# airball_sensor_board_v4.net
KiCad netlist of a schematic drawn in EAGLE
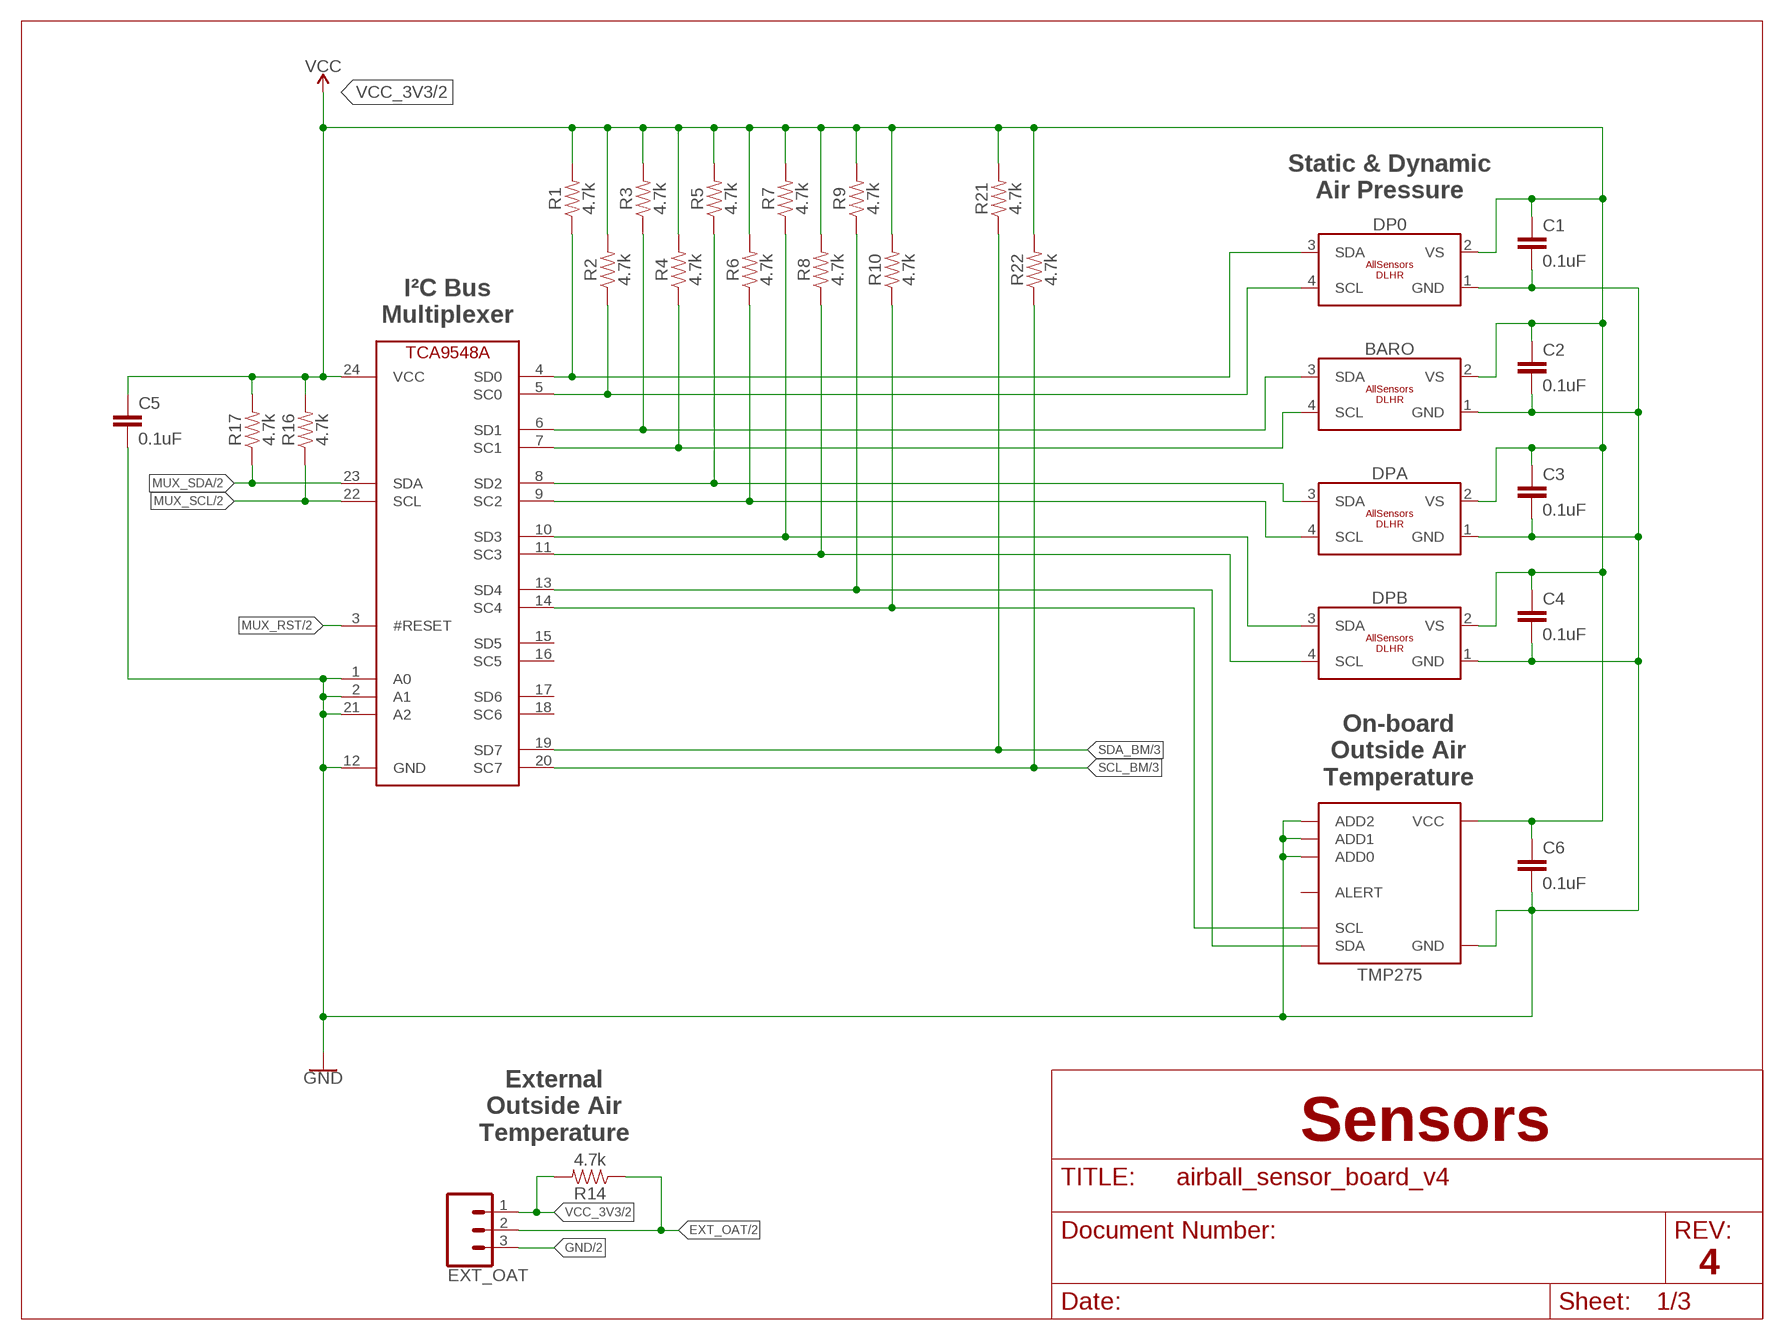
[diagram p0: schematic, sheet 1]
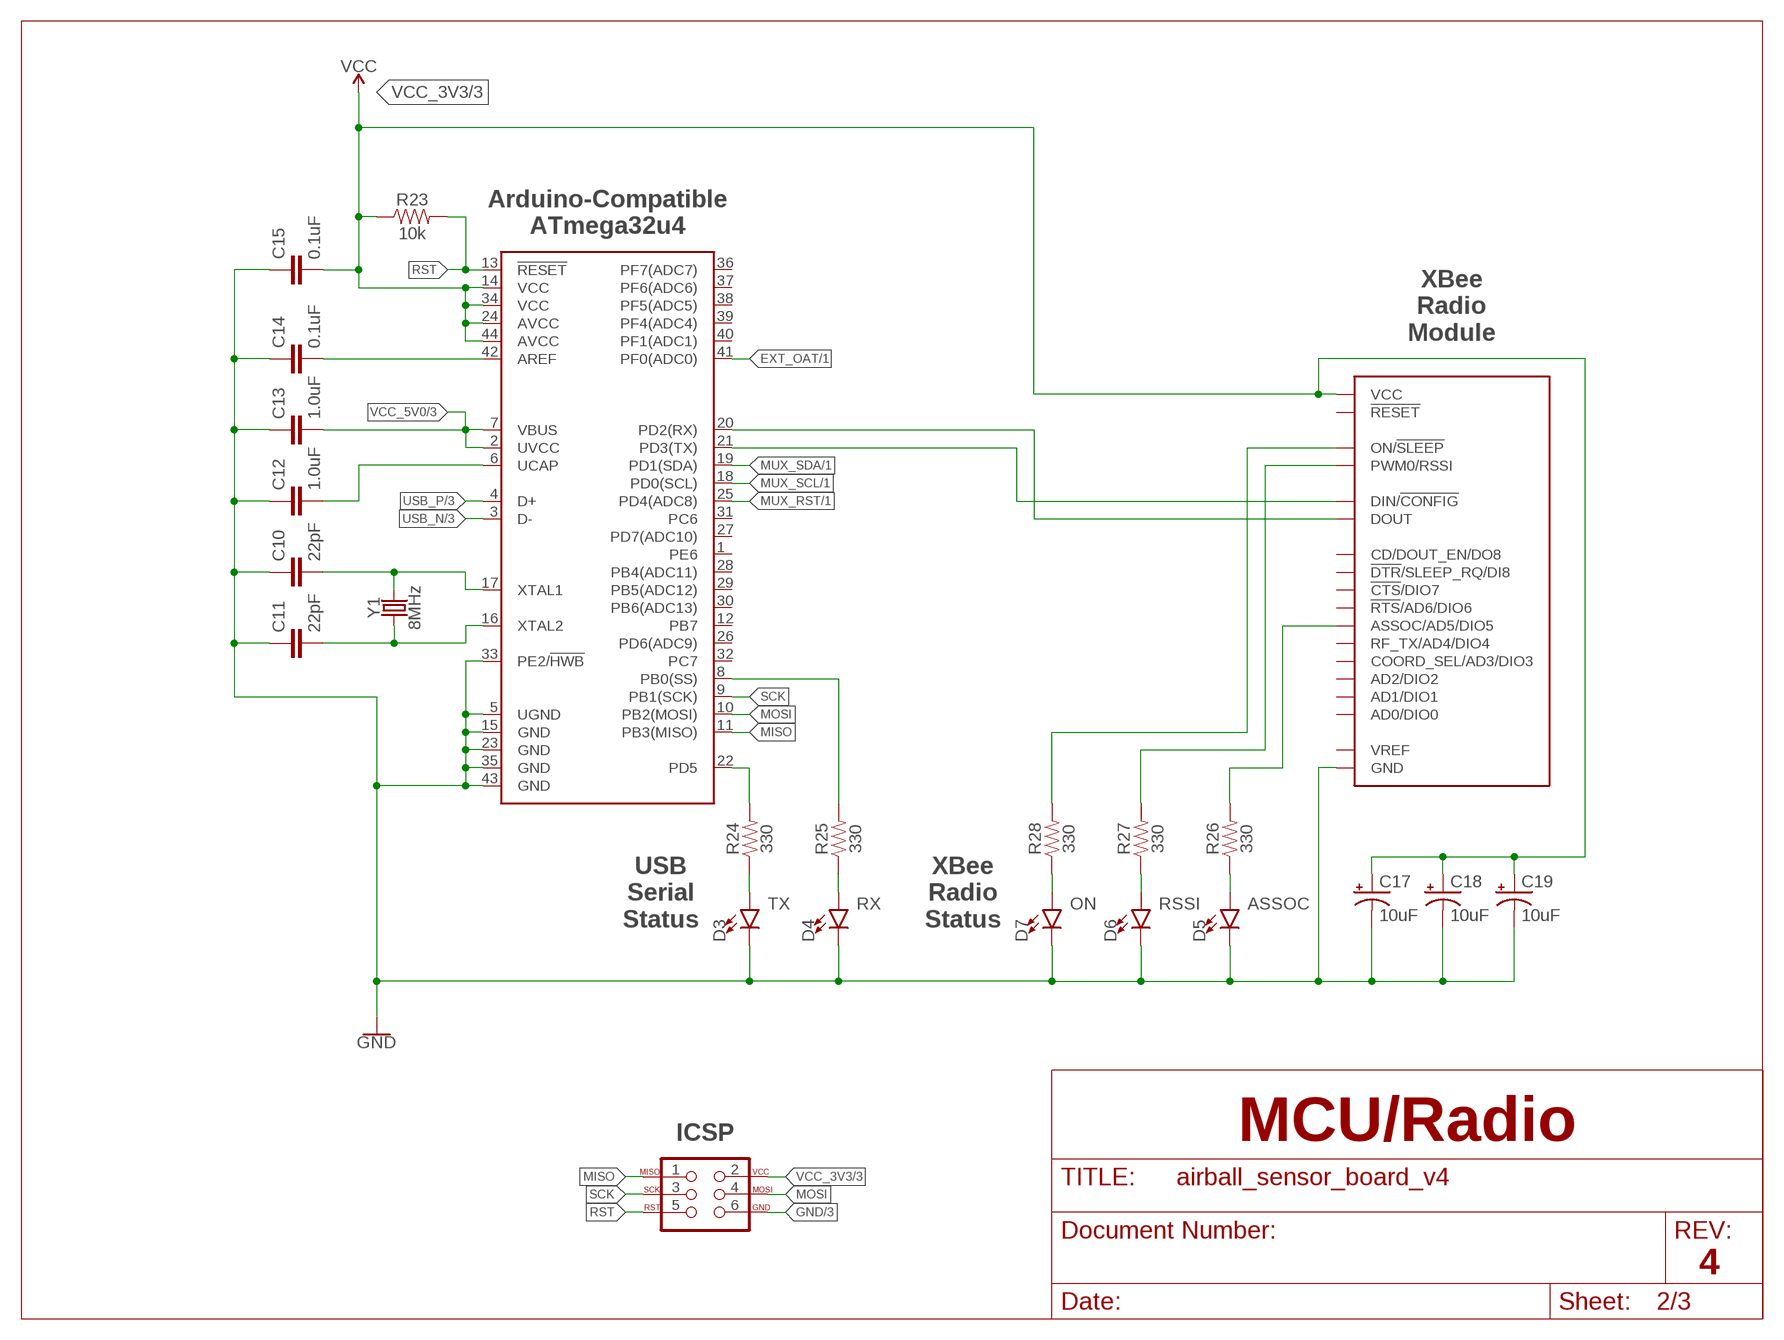
[diagram p1: schematic, sheet 2]
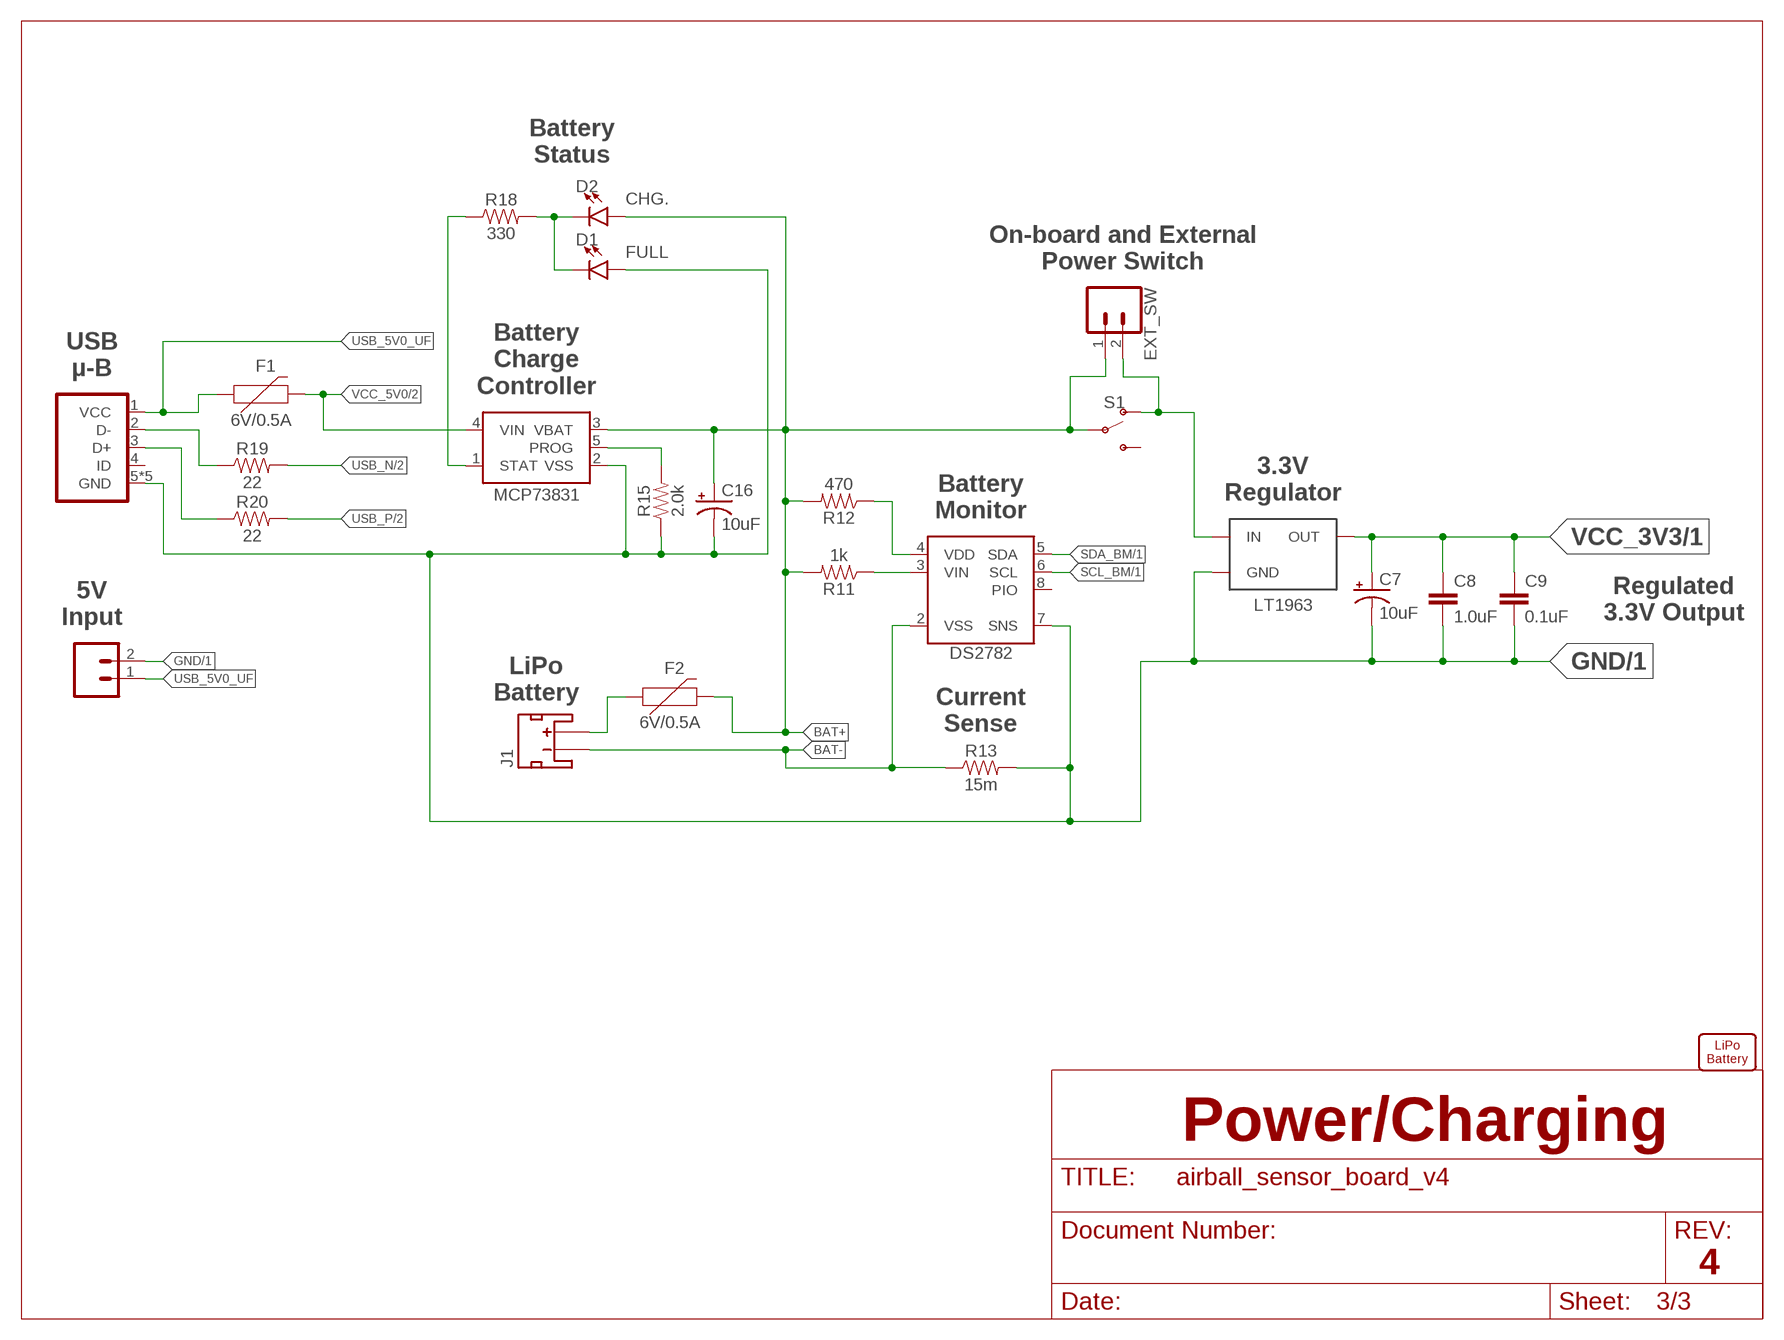
[diagram p2: schematic, sheet 3]

(export (version "E")
  (design (tool "Eeschema 10.0.6"))
  (components
    (comp (ref "BM")
      (value "DS2782")
      (footprint "eagle-import:TSSOP8")
      (libsource (lib "eagle-import") (part "DS2782"))
    )
    (comp (ref "C7")
      (value "10uF")
      (footprint "eagle-import:EIA3216")
      (libsource (lib "eagle-import") (part "10UF-POLAR-EIA3216-16V-10%(TANT)"))
    )
    (comp (ref "C8")
      (value "1.0uF")
      (footprint "eagle-import:0603")
      (libsource (lib "eagle-import") (part "1.0UF-0603-16V-10%"))
    )
    (comp (ref "C9")
      (value "0.1uF")
      (footprint "eagle-import:0603")
      (libsource (lib "eagle-import") (part "0.1UF-0603-25V-5%"))
    )
    (comp (ref "C16")
      (value "10uF")
      (footprint "eagle-import:EIA3216")
      (libsource (lib "eagle-import") (part "10UF-POLAR-EIA3216-16V-10%(TANT)"))
    )
    (comp (ref "CC")
      (value "MCP73831")
      (footprint "eagle-import:SOT23-5")
      (libsource (lib "eagle-import") (part "MCP73831"))
    )
    (comp (ref "D1")
      (value "LED0603")
      (footprint "eagle-import:LED-0603")
      (libsource (lib "eagle-import") (part "LED0603"))
    )
    (comp (ref "D2")
      (value "LED0603")
      (footprint "eagle-import:LED-0603")
      (libsource (lib "eagle-import") (part "LED0603"))
    )
    (comp (ref "EXT_POWER")
      (value "CONN_02")
      (footprint "eagle-import:1X02")
      (libsource (lib "eagle-import") (part "CONN_02"))
    )
    (comp (ref "EXT_SW")
      (value "CONN_02")
      (footprint "eagle-import:1X02")
      (libsource (lib "eagle-import") (part "CONN_02"))
    )
    (comp (ref "F1")
      (value "6V/0.5A")
      (footprint "eagle-import:1206")
      (libsource (lib "eagle-import") (part "PPTC_HALF-AMP"))
    )
    (comp (ref "F2")
      (value "6V/0.5A")
      (footprint "eagle-import:1206")
      (libsource (lib "eagle-import") (part "PPTC_HALF-AMP"))
    )
    (comp (ref "J1")
      (value "JST_2MM_MALE")
      (footprint "eagle-import:JST-2-SMD")
      (libsource (lib "eagle-import") (part "JST_2MM_MALE"))
    )
    (comp (ref "JP1")
      (value "USB_MICROB_PLUG")
      (footprint "eagle-import:USB_MICRO_B_TYCO")
      (libsource (lib "eagle-import") (part "USB_MICROB_PLUG"))
    )
    (comp (ref "R11")
      (value "1k")
      (footprint "eagle-import:0603")
      (libsource (lib "eagle-import") (part "1KOHM-0603-1/10W-1%"))
    )
    (comp (ref "R12")
      (value "470")
      (footprint "eagle-import:0603")
      (libsource (lib "eagle-import") (part "470OHM-0603-1/10W-1%"))
    )
    (comp (ref "R13")
      (value "15m")
      (footprint "eagle-import:1206")
      (libsource (lib "eagle-import") (part "RESISTOR1206"))
    )
    (comp (ref "R15")
      (value "2.0k")
      (footprint "eagle-import:0603")
      (libsource (lib "eagle-import") (part "2.0KOHM-0603-1/10W-5%"))
    )
    (comp (ref "R18")
      (value "330")
      (footprint "eagle-import:0603")
      (libsource (lib "eagle-import") (part "330OHM-0603-1/10W-1%"))
    )
    (comp (ref "R19")
      (value "22")
      (footprint "eagle-import:0603")
      (libsource (lib "eagle-import") (part "22OHM-0603-1/10W-1%"))
    )
    (comp (ref "R20")
      (value "22")
      (footprint "eagle-import:0603")
      (libsource (lib "eagle-import") (part "22OHM-0603-1/10W-1%"))
    )
    (comp (ref "S1")
      (value "SWITCH-SPDT-SMD-RIGHT-ANGLE")
      (footprint "eagle-import:SWITCH_SPST_SMD_A")
      (libsource (lib "eagle-import") (part "SWITCH-SPDT-SMD-RIGHT-ANGLE"))
    )
    (comp (ref "U$3")
      (value "LIPO_BATTERY_OUTLINE-1000MAH")
      (footprint "eagle-import:SPARKFUN_LIPO_1000MAH")
      (libsource (lib "eagle-import") (part "LIPO_BATTERY_OUTLINE-1000MAH"))
    )
    (comp (ref "VREG")
      (value "LT1963")
      (footprint "eagle-import:SOT223-3")
      (libsource (lib "eagle-import") (part "LT1963"))
    )
    (comp (ref "C10")
      (value "22pF")
      (footprint "eagle-import:0603")
      (libsource (lib "eagle-import") (part "22PF-0603-50V-5%"))
    )
    (comp (ref "C11")
      (value "22pF")
      (footprint "eagle-import:0603")
      (libsource (lib "eagle-import") (part "22PF-0603-50V-5%"))
    )
    (comp (ref "C12")
      (value "1.0uF")
      (footprint "eagle-import:0603")
      (libsource (lib "eagle-import") (part "1.0UF-0603-16V-10%"))
    )
    (comp (ref "C13")
      (value "1.0uF")
      (footprint "eagle-import:0603")
      (libsource (lib "eagle-import") (part "1.0UF-0603-16V-10%"))
    )
    (comp (ref "C14")
      (value "0.1uF")
      (footprint "eagle-import:0603")
      (libsource (lib "eagle-import") (part "0.1UF-0603-25V-5%"))
    )
    (comp (ref "C15")
      (value "0.1uF")
      (footprint "eagle-import:0603")
      (libsource (lib "eagle-import") (part "0.1UF-0603-25V-5%"))
    )
    (comp (ref "C17")
      (value "10uF")
      (footprint "eagle-import:EIA3216")
      (libsource (lib "eagle-import") (part "10UF-POLAR-EIA3216-16V-10%(TANT)"))
    )
    (comp (ref "C18")
      (value "10uF")
      (footprint "eagle-import:EIA3216")
      (libsource (lib "eagle-import") (part "10UF-POLAR-EIA3216-16V-10%(TANT)"))
    )
    (comp (ref "C19")
      (value "10uF")
      (footprint "eagle-import:EIA3216")
      (libsource (lib "eagle-import") (part "10UF-POLAR-EIA3216-16V-10%(TANT)"))
    )
    (comp (ref "D3")
      (value "LED0603")
      (footprint "eagle-import:LED-0603")
      (libsource (lib "eagle-import") (part "LED0603"))
    )
    (comp (ref "D4")
      (value "LED0603")
      (footprint "eagle-import:LED-0603")
      (libsource (lib "eagle-import") (part "LED0603"))
    )
    (comp (ref "D5")
      (value "LED0603")
      (footprint "eagle-import:LED-0603")
      (libsource (lib "eagle-import") (part "LED0603"))
    )
    (comp (ref "D6")
      (value "LED0603")
      (footprint "eagle-import:LED-0603")
      (libsource (lib "eagle-import") (part "LED0603"))
    )
    (comp (ref "D7")
      (value "LED0603")
      (footprint "eagle-import:LED-0603")
      (libsource (lib "eagle-import") (part "LED0603"))
    )
    (comp (ref "ICSP")
      (value "AVR_SPI_PROG_3X2PTH")
      (footprint "eagle-import:2X3")
      (libsource (lib "eagle-import") (part "AVR_SPI_PROG_3X2PTH"))
    )
    (comp (ref "MCU")
      (value "32U4")
      (footprint "eagle-import:TQFP44")
      (libsource (lib "eagle-import") (part "ATMEGA32U4TQFP-44"))
    )
    (comp (ref "R23")
      (value "10k")
      (footprint "eagle-import:0603")
      (libsource (lib "eagle-import") (part "10KOHM-0603-1/10W-1%"))
    )
    (comp (ref "R24")
      (value "330")
      (footprint "eagle-import:0603")
      (libsource (lib "eagle-import") (part "330OHM-0603-1/10W-1%"))
    )
    (comp (ref "R25")
      (value "330")
      (footprint "eagle-import:0603")
      (libsource (lib "eagle-import") (part "330OHM-0603-1/10W-1%"))
    )
    (comp (ref "R26")
      (value "330")
      (footprint "eagle-import:0603")
      (libsource (lib "eagle-import") (part "330OHM-0603-1/10W-1%"))
    )
    (comp (ref "R27")
      (value "330")
      (footprint "eagle-import:0603")
      (libsource (lib "eagle-import") (part "330OHM-0603-1/10W-1%"))
    )
    (comp (ref "R28")
      (value "330")
      (footprint "eagle-import:0603")
      (libsource (lib "eagle-import") (part "330OHM-0603-1/10W-1%"))
    )
    (comp (ref "XBEE")
      (value "XBEE-PRO-SMD")
      (footprint "eagle-import:XBEE-PRO-SMD")
      (libsource (lib "eagle-import") (part "XBEE-PRO-SMD"))
    )
    (comp (ref "Y1")
      (value "8MHz")
      (footprint "eagle-import:CRYSTAL-SMD-5X3.2-4PAD")
      (libsource (lib "eagle-import") (part "CRYSTAL-8MHZSMD-5X3.2"))
    )
    (comp (ref "BARO")
      (value "ALLSENSORS_DLHR_I2C-E1BD")
      (footprint "eagle-import:ALLSENSORS_E1BD")
      (libsource (lib "eagle-import") (part "ALLSENSORS_DLHR_I2C-E1BD"))
    )
    (comp (ref "C1")
      (value "0.1uF")
      (footprint "eagle-import:0603")
      (libsource (lib "eagle-import") (part "0.1UF-0603-25V-5%"))
    )
    (comp (ref "C2")
      (value "0.1uF")
      (footprint "eagle-import:0603")
      (libsource (lib "eagle-import") (part "0.1UF-0603-25V-5%"))
    )
    (comp (ref "C3")
      (value "0.1uF")
      (footprint "eagle-import:0603")
      (libsource (lib "eagle-import") (part "0.1UF-0603-25V-5%"))
    )
    (comp (ref "C4")
      (value "0.1uF")
      (footprint "eagle-import:0603")
      (libsource (lib "eagle-import") (part "0.1UF-0603-25V-5%"))
    )
    (comp (ref "C5")
      (value "0.1uF")
      (footprint "eagle-import:0603")
      (libsource (lib "eagle-import") (part "0.1UF-0603-25V-5%"))
    )
    (comp (ref "C6")
      (value "0.1uF")
      (footprint "eagle-import:0603")
      (libsource (lib "eagle-import") (part "0.1UF-0603-25V-5%"))
    )
    (comp (ref "DP0")
      (value "ALLSENSORS_DLHR_I2C-E1BD")
      (footprint "eagle-import:ALLSENSORS_E1BD")
      (libsource (lib "eagle-import") (part "ALLSENSORS_DLHR_I2C-E1BD"))
    )
    (comp (ref "DPA")
      (value "ALLSENSORS_DLHR_I2C-E1BD")
      (footprint "eagle-import:ALLSENSORS_E1BD")
      (libsource (lib "eagle-import") (part "ALLSENSORS_DLHR_I2C-E1BD"))
    )
    (comp (ref "DPB")
      (value "ALLSENSORS_DLHR_I2C-E1BD")
      (footprint "eagle-import:ALLSENSORS_E1BD")
      (libsource (lib "eagle-import") (part "ALLSENSORS_DLHR_I2C-E1BD"))
    )
    (comp (ref "EXT_OAT")
      (value "CONN_03")
      (footprint "eagle-import:1X03")
      (libsource (lib "eagle-import") (part "CONN_03"))
    )
    (comp (ref "MUX")
      (value "TCA9548ATSSOP24")
      (footprint "eagle-import:TSSOP24")
      (libsource (lib "eagle-import") (part "TCA9548ATSSOP24"))
    )
    (comp (ref "OAT")
      (value "TMP275")
      (footprint "eagle-import:SOIC8")
      (libsource (lib "eagle-import") (part "LM75-8PIN"))
    )
    (comp (ref "R1")
      (value "4.7k")
      (footprint "eagle-import:0603")
      (libsource (lib "eagle-import") (part "4.7KOHM-0603-1/10W-1%"))
    )
    (comp (ref "R2")
      (value "4.7k")
      (footprint "eagle-import:0603")
      (libsource (lib "eagle-import") (part "4.7KOHM-0603-1/10W-1%"))
    )
    (comp (ref "R3")
      (value "4.7k")
      (footprint "eagle-import:0603")
      (libsource (lib "eagle-import") (part "4.7KOHM-0603-1/10W-1%"))
    )
    (comp (ref "R4")
      (value "4.7k")
      (footprint "eagle-import:0603")
      (libsource (lib "eagle-import") (part "4.7KOHM-0603-1/10W-1%"))
    )
    (comp (ref "R5")
      (value "4.7k")
      (footprint "eagle-import:0603")
      (libsource (lib "eagle-import") (part "4.7KOHM-0603-1/10W-1%"))
    )
    (comp (ref "R6")
      (value "4.7k")
      (footprint "eagle-import:0603")
      (libsource (lib "eagle-import") (part "4.7KOHM-0603-1/10W-1%"))
    )
    (comp (ref "R7")
      (value "4.7k")
      (footprint "eagle-import:0603")
      (libsource (lib "eagle-import") (part "4.7KOHM-0603-1/10W-1%"))
    )
    (comp (ref "R8")
      (value "4.7k")
      (footprint "eagle-import:0603")
      (libsource (lib "eagle-import") (part "4.7KOHM-0603-1/10W-1%"))
    )
    (comp (ref "R9")
      (value "4.7k")
      (footprint "eagle-import:0603")
      (libsource (lib "eagle-import") (part "4.7KOHM-0603-1/10W-1%"))
    )
    (comp (ref "R10")
      (value "4.7k")
      (footprint "eagle-import:0603")
      (libsource (lib "eagle-import") (part "4.7KOHM-0603-1/10W-1%"))
    )
    (comp (ref "R14")
      (value "4.7k")
      (footprint "eagle-import:0603")
      (libsource (lib "eagle-import") (part "4.7KOHM-0603-1/10W-1%"))
    )
    (comp (ref "R16")
      (value "4.7k")
      (footprint "eagle-import:0603")
      (libsource (lib "eagle-import") (part "4.7KOHM-0603-1/10W-1%"))
    )
    (comp (ref "R17")
      (value "4.7k")
      (footprint "eagle-import:0603")
      (libsource (lib "eagle-import") (part "4.7KOHM-0603-1/10W-1%"))
    )
    (comp (ref "R21")
      (value "4.7k")
      (footprint "eagle-import:0603")
      (libsource (lib "eagle-import") (part "4.7KOHM-0603-1/10W-1%"))
    )
    (comp (ref "R22")
      (value "4.7k")
      (footprint "eagle-import:0603")
      (libsource (lib "eagle-import") (part "4.7KOHM-0603-1/10W-1%"))
    )
  )
  (nets
    (net (code "1") (name "BAT+") (class "Default")
      (node (ref "C16") (pin "+") (pinfunction "+_+") (pintype "passive"))
      (node (ref "CC") (pin "3") (pinfunction "VBAT_3") (pintype "power_in"))
      (node (ref "D2") (pin "A") (pinfunction "A_A") (pintype "passive"))
      (node (ref "EXT_SW") (pin "1") (pinfunction "1_1") (pintype "passive"))
      (node (ref "F2") (pin "2") (pinfunction "2_2") (pintype "bidirectional"))
      (node (ref "R11") (pin "2") (pinfunction "2_2") (pintype "passive"))
      (node (ref "R12") (pin "2") (pinfunction "2_2") (pintype "passive"))
      (node (ref "S1") (pin "2") (pinfunction "P_2") (pintype "passive"))
    )
    (net (code "2") (name "BAT-") (class "Default")
      (node (ref "BM") (pin "2") (pinfunction "VSS_2") (pintype "power_in"))
      (node (ref "J1") (pin "1") (pinfunction "-_1") (pintype "bidirectional"))
      (node (ref "R13") (pin "1") (pinfunction "1_1") (pintype "passive"))
    )
    (net (code "3") (name "EXT_OAT") (class "Default")
      (node (ref "EXT_OAT") (pin "2") (pinfunction "2_2") (pintype "passive"))
      (node (ref "MCU") (pin "41") (pinfunction "PF0(ADC0)_41") (pintype "bidirectional"))
      (node (ref "R14") (pin "1") (pinfunction "1_1") (pintype "passive"))
    )
    (net (code "4") (name "GND") (class "Default")
      (node (ref "BARO") (pin "1") (pinfunction "GND_1") (pintype "power_in"))
      (node (ref "BM") (pin "7") (pinfunction "SNS_7") (pintype "power_in"))
      (node (ref "C1") (pin "2") (pinfunction "2_2") (pintype "passive"))
      (node (ref "C10") (pin "1") (pinfunction "1_1") (pintype "passive"))
      (node (ref "C11") (pin "1") (pinfunction "1_1") (pintype "passive"))
      (node (ref "C12") (pin "1") (pinfunction "1_1") (pintype "passive"))
      (node (ref "C13") (pin "1") (pinfunction "1_1") (pintype "passive"))
      (node (ref "C14") (pin "1") (pinfunction "1_1") (pintype "passive"))
      (node (ref "C15") (pin "1") (pinfunction "1_1") (pintype "passive"))
      (node (ref "C16") (pin "-") (pinfunction "-_-") (pintype "passive"))
      (node (ref "C17") (pin "-") (pinfunction "-_-") (pintype "passive"))
      (node (ref "C18") (pin "-") (pinfunction "-_-") (pintype "passive"))
      (node (ref "C19") (pin "-") (pinfunction "-_-") (pintype "passive"))
      (node (ref "C2") (pin "2") (pinfunction "2_2") (pintype "passive"))
      (node (ref "C3") (pin "2") (pinfunction "2_2") (pintype "passive"))
      (node (ref "C4") (pin "2") (pinfunction "2_2") (pintype "passive"))
      (node (ref "C5") (pin "2") (pinfunction "2_2") (pintype "passive"))
      (node (ref "C6") (pin "2") (pinfunction "2_2") (pintype "passive"))
      (node (ref "C7") (pin "-") (pinfunction "-_-") (pintype "passive"))
      (node (ref "C8") (pin "2") (pinfunction "2_2") (pintype "passive"))
      (node (ref "C9") (pin "2") (pinfunction "2_2") (pintype "passive"))
      (node (ref "CC") (pin "2") (pinfunction "VSS_2") (pintype "power_in"))
      (node (ref "D1") (pin "A") (pinfunction "A_A") (pintype "passive"))
      (node (ref "D3") (pin "C") (pinfunction "C_C") (pintype "passive"))
      (node (ref "D4") (pin "C") (pinfunction "C_C") (pintype "passive"))
      (node (ref "D5") (pin "C") (pinfunction "C_C") (pintype "passive"))
      (node (ref "D6") (pin "C") (pinfunction "C_C") (pintype "passive"))
      (node (ref "D7") (pin "C") (pinfunction "C_C") (pintype "passive"))
      (node (ref "DP0") (pin "1") (pinfunction "GND_1") (pintype "power_in"))
      (node (ref "DPA") (pin "1") (pinfunction "GND_1") (pintype "power_in"))
      (node (ref "DPB") (pin "1") (pinfunction "GND_1") (pintype "power_in"))
      (node (ref "EXT_OAT") (pin "3") (pinfunction "3_3") (pintype "passive"))
      (node (ref "EXT_POWER") (pin "2") (pinfunction "2_2") (pintype "passive"))
      (node (ref "ICSP") (pin "6") (pinfunction "6_6") (pintype "passive"))
      (node (ref "JP1") (pin "5") (pinfunction "GND_5") (pintype "bidirectional"))
      (node (ref "JP1") (pin "SH@1") (pinfunction "GND_SH@1") (pintype "bidirectional"))
      (node (ref "JP1") (pin "SH@2") (pinfunction "GND_SH@2") (pintype "bidirectional"))
      (node (ref "JP1") (pin "SH@3") (pinfunction "GND_SH@3") (pintype "bidirectional"))
      (node (ref "JP1") (pin "SH@4") (pinfunction "GND_SH@4") (pintype "bidirectional"))
      (node (ref "MCU") (pin "15") (pinfunction "GND_15") (pintype "bidirectional"))
      (node (ref "MCU") (pin "23") (pinfunction "GND_23") (pintype "bidirectional"))
      (node (ref "MCU") (pin "33") (pinfunction "PE2/~{HWB}_33") (pintype "bidirectional"))
      (node (ref "MCU") (pin "35") (pinfunction "GND_35") (pintype "bidirectional"))
      (node (ref "MCU") (pin "43") (pinfunction "GND_43") (pintype "bidirectional"))
      (node (ref "MCU") (pin "5") (pinfunction "UGND_5") (pintype "bidirectional"))
      (node (ref "MUX") (pin "1") (pinfunction "A0_1") (pintype "bidirectional"))
      (node (ref "MUX") (pin "12") (pinfunction "GND_12") (pintype "bidirectional"))
      (node (ref "MUX") (pin "2") (pinfunction "A1_2") (pintype "bidirectional"))
      (node (ref "MUX") (pin "21") (pinfunction "A2_21") (pintype "bidirectional"))
      (node (ref "OAT") (pin "4") (pinfunction "GND_4") (pintype "power_in"))
      (node (ref "OAT") (pin "5") (pinfunction "ADD2_5") (pintype "input"))
      (node (ref "OAT") (pin "6") (pinfunction "ADD1_6") (pintype "input"))
      (node (ref "OAT") (pin "7") (pinfunction "ADD0_7") (pintype "input"))
      (node (ref "R13") (pin "2") (pinfunction "2_2") (pintype "passive"))
      (node (ref "R15") (pin "1") (pinfunction "1_1") (pintype "passive"))
      (node (ref "VREG") (pin "2") (pinfunction "GND_2") (pintype "power_in"))
      (node (ref "VREG") (pin "TAB") (pinfunction "GND_TAB") (pintype "power_in"))
      (node (ref "XBEE") (pin "10") (pinfunction "GND_10") (pintype "power_in"))
    )
    (net (code "5") (name "MISO") (class "Default")
      (node (ref "ICSP") (pin "1") (pinfunction "1_1") (pintype "passive"))
      (node (ref "MCU") (pin "11") (pinfunction "PB3(MISO)_11") (pintype "bidirectional"))
    )
    (net (code "6") (name "MOSI") (class "Default")
      (node (ref "ICSP") (pin "4") (pinfunction "4_4") (pintype "passive"))
      (node (ref "MCU") (pin "10") (pinfunction "PB2(MOSI)_10") (pintype "bidirectional"))
    )
    (net (code "7") (name "MUX_RST") (class "Default")
      (node (ref "MCU") (pin "25") (pinfunction "PD4(ADC8)_25") (pintype "bidirectional"))
      (node (ref "MUX") (pin "3") (pinfunction "#RESET_3") (pintype "bidirectional"))
    )
    (net (code "8") (name "MUX_SCL") (class "Default")
      (node (ref "MCU") (pin "18") (pinfunction "PD0(SCL)_18") (pintype "bidirectional"))
      (node (ref "MUX") (pin "22") (pinfunction "SCL_22") (pintype "bidirectional"))
      (node (ref "R16") (pin "1") (pinfunction "1_1") (pintype "passive"))
    )
    (net (code "9") (name "MUX_SDA") (class "Default")
      (node (ref "MCU") (pin "19") (pinfunction "PD1(SDA)_19") (pintype "bidirectional"))
      (node (ref "MUX") (pin "23") (pinfunction "SDA_23") (pintype "bidirectional"))
      (node (ref "R17") (pin "1") (pinfunction "1_1") (pintype "passive"))
    )
    (net (code "10") (name "Net-(BARO-SCL)") (class "Default")
      (node (ref "BARO") (pin "4") (pinfunction "SCL_4") (pintype "bidirectional"))
      (node (ref "MUX") (pin "7") (pinfunction "SC1_7") (pintype "bidirectional"))
      (node (ref "R4") (pin "1") (pinfunction "1_1") (pintype "passive"))
    )
    (net (code "11") (name "Net-(BARO-SDA)") (class "Default")
      (node (ref "BARO") (pin "3") (pinfunction "SDA_3") (pintype "bidirectional"))
      (node (ref "MUX") (pin "6") (pinfunction "SD1_6") (pintype "bidirectional"))
      (node (ref "R3") (pin "1") (pinfunction "1_1") (pintype "passive"))
    )
    (net (code "12") (name "Net-(BM-VDD)") (class "Default")
      (node (ref "BM") (pin "4") (pinfunction "VDD_4") (pintype "power_in"))
      (node (ref "R12") (pin "1") (pinfunction "1_1") (pintype "passive"))
    )
    (net (code "13") (name "Net-(BM-VIN)") (class "Default")
      (node (ref "BM") (pin "3") (pinfunction "VIN_3") (pintype "power_in"))
      (node (ref "R11") (pin "1") (pinfunction "1_1") (pintype "passive"))
    )
    (net (code "14") (name "Net-(CC-PROG)") (class "Default")
      (node (ref "CC") (pin "5") (pinfunction "PROG_5") (pintype "input"))
      (node (ref "R15") (pin "2") (pinfunction "2_2") (pintype "passive"))
    )
    (net (code "15") (name "Net-(CC-STAT)") (class "Default")
      (node (ref "CC") (pin "1") (pinfunction "STAT_1") (pintype "output"))
      (node (ref "R18") (pin "1") (pinfunction "1_1") (pintype "passive"))
    )
    (net (code "16") (name "Net-(D1-PadC)") (class "Default")
      (node (ref "D1") (pin "C") (pinfunction "C_C") (pintype "passive"))
      (node (ref "D2") (pin "C") (pinfunction "C_C") (pintype "passive"))
      (node (ref "R18") (pin "2") (pinfunction "2_2") (pintype "passive"))
    )
    (net (code "17") (name "Net-(D3-PadA)") (class "Default")
      (node (ref "D3") (pin "A") (pinfunction "A_A") (pintype "passive"))
      (node (ref "R24") (pin "1") (pinfunction "1_1") (pintype "passive"))
    )
    (net (code "18") (name "Net-(D4-PadA)") (class "Default")
      (node (ref "D4") (pin "A") (pinfunction "A_A") (pintype "passive"))
      (node (ref "R25") (pin "1") (pinfunction "1_1") (pintype "passive"))
    )
    (net (code "19") (name "Net-(D5-PadA)") (class "Default")
      (node (ref "D5") (pin "A") (pinfunction "A_A") (pintype "passive"))
      (node (ref "R26") (pin "1") (pinfunction "1_1") (pintype "passive"))
    )
    (net (code "20") (name "Net-(D6-PadA)") (class "Default")
      (node (ref "D6") (pin "A") (pinfunction "A_A") (pintype "passive"))
      (node (ref "R27") (pin "1") (pinfunction "1_1") (pintype "passive"))
    )
    (net (code "21") (name "Net-(D7-PadA)") (class "Default")
      (node (ref "D7") (pin "A") (pinfunction "A_A") (pintype "passive"))
      (node (ref "R28") (pin "1") (pinfunction "1_1") (pintype "passive"))
    )
    (net (code "22") (name "Net-(DP0-SCL)") (class "Default")
      (node (ref "DP0") (pin "4") (pinfunction "SCL_4") (pintype "bidirectional"))
      (node (ref "MUX") (pin "5") (pinfunction "SC0_5") (pintype "bidirectional"))
      (node (ref "R2") (pin "1") (pinfunction "1_1") (pintype "passive"))
    )
    (net (code "23") (name "Net-(DP0-SDA)") (class "Default")
      (node (ref "DP0") (pin "3") (pinfunction "SDA_3") (pintype "bidirectional"))
      (node (ref "MUX") (pin "4") (pinfunction "SD0_4") (pintype "bidirectional"))
      (node (ref "R1") (pin "1") (pinfunction "1_1") (pintype "passive"))
    )
    (net (code "24") (name "Net-(DPA-SCL)") (class "Default")
      (node (ref "DPA") (pin "4") (pinfunction "SCL_4") (pintype "bidirectional"))
      (node (ref "MUX") (pin "9") (pinfunction "SC2_9") (pintype "bidirectional"))
      (node (ref "R6") (pin "1") (pinfunction "1_1") (pintype "passive"))
    )
    (net (code "25") (name "Net-(DPA-SDA)") (class "Default")
      (node (ref "DPA") (pin "3") (pinfunction "SDA_3") (pintype "bidirectional"))
      (node (ref "MUX") (pin "8") (pinfunction "SD2_8") (pintype "bidirectional"))
      (node (ref "R5") (pin "1") (pinfunction "1_1") (pintype "passive"))
    )
    (net (code "26") (name "Net-(DPB-SCL)") (class "Default")
      (node (ref "DPB") (pin "4") (pinfunction "SCL_4") (pintype "bidirectional"))
      (node (ref "MUX") (pin "11") (pinfunction "SC3_11") (pintype "bidirectional"))
      (node (ref "R8") (pin "1") (pinfunction "1_1") (pintype "passive"))
    )
    (net (code "27") (name "Net-(DPB-SDA)") (class "Default")
      (node (ref "DPB") (pin "3") (pinfunction "SDA_3") (pintype "bidirectional"))
      (node (ref "MUX") (pin "10") (pinfunction "SD3_10") (pintype "bidirectional"))
      (node (ref "R7") (pin "1") (pinfunction "1_1") (pintype "passive"))
    )
    (net (code "28") (name "Net-(J1-+)") (class "Default")
      (node (ref "F2") (pin "1") (pinfunction "1_1") (pintype "bidirectional"))
      (node (ref "J1") (pin "2") (pinfunction "+_2") (pintype "bidirectional"))
    )
    (net (code "29") (name "Net-(JP1-D+)") (class "Default")
      (node (ref "JP1") (pin "3") (pinfunction "D+_3") (pintype "bidirectional"))
      (node (ref "R20") (pin "1") (pinfunction "1_1") (pintype "passive"))
    )
    (net (code "30") (name "Net-(JP1-D-)") (class "Default")
      (node (ref "JP1") (pin "2") (pinfunction "D-_2") (pintype "bidirectional"))
      (node (ref "R19") (pin "1") (pinfunction "1_1") (pintype "passive"))
    )
    (net (code "31") (name "Net-(MCU-AREF)") (class "Default")
      (node (ref "C14") (pin "2") (pinfunction "2_2") (pintype "passive"))
      (node (ref "MCU") (pin "42") (pinfunction "AREF_42") (pintype "bidirectional"))
    )
    (net (code "32") (name "Net-(MCU-PB0(SS))") (class "Default")
      (node (ref "MCU") (pin "8") (pinfunction "PB0(SS)_8") (pintype "bidirectional"))
      (node (ref "R25") (pin "2") (pinfunction "2_2") (pintype "passive"))
    )
    (net (code "33") (name "Net-(MCU-PD2(RX))") (class "Default")
      (node (ref "MCU") (pin "20") (pinfunction "PD2(RX)_20") (pintype "bidirectional"))
      (node (ref "XBEE") (pin "2") (pinfunction "DOUT_2") (pintype "output"))
    )
    (net (code "34") (name "Net-(MCU-PD3(TX))") (class "Default")
      (node (ref "MCU") (pin "21") (pinfunction "PD3(TX)_21") (pintype "bidirectional"))
      (node (ref "XBEE") (pin "3") (pinfunction "DIN/~{CONFIG}_3") (pintype "input"))
    )
    (net (code "35") (name "Net-(MCU-PD5)") (class "Default")
      (node (ref "MCU") (pin "22") (pinfunction "PD5_22") (pintype "bidirectional"))
      (node (ref "R24") (pin "2") (pinfunction "2_2") (pintype "passive"))
    )
    (net (code "36") (name "Net-(MCU-UCAP)") (class "Default")
      (node (ref "C12") (pin "2") (pinfunction "2_2") (pintype "passive"))
      (node (ref "MCU") (pin "6") (pinfunction "UCAP_6") (pintype "bidirectional"))
    )
    (net (code "37") (name "Net-(MCU-XTAL1)") (class "Default")
      (node (ref "C10") (pin "2") (pinfunction "2_2") (pintype "passive"))
      (node (ref "MCU") (pin "17") (pinfunction "XTAL1_17") (pintype "bidirectional"))
      (node (ref "Y1") (pin "3") (pinfunction "2_3") (pintype "passive"))
    )
    (net (code "38") (name "Net-(MCU-XTAL2)") (class "Default")
      (node (ref "C11") (pin "2") (pinfunction "2_2") (pintype "passive"))
      (node (ref "MCU") (pin "16") (pinfunction "XTAL2_16") (pintype "bidirectional"))
      (node (ref "Y1") (pin "1") (pinfunction "1_1") (pintype "passive"))
    )
    (net (code "39") (name "Net-(MUX-SC4)") (class "Default")
      (node (ref "MUX") (pin "14") (pinfunction "SC4_14") (pintype "bidirectional"))
      (node (ref "OAT") (pin "2") (pinfunction "SCL_2") (pintype "input"))
      (node (ref "R10") (pin "1") (pinfunction "1_1") (pintype "passive"))
    )
    (net (code "40") (name "Net-(MUX-SD4)") (class "Default")
      (node (ref "MUX") (pin "13") (pinfunction "SD4_13") (pintype "bidirectional"))
      (node (ref "OAT") (pin "1") (pinfunction "SDA_1") (pintype "bidirectional"))
      (node (ref "R9") (pin "1") (pinfunction "1_1") (pintype "passive"))
    )
    (net (code "41") (name "Net-(S1-O)") (class "Default")
      (node (ref "EXT_SW") (pin "2") (pinfunction "2_2") (pintype "passive"))
      (node (ref "S1") (pin "1") (pinfunction "O_1") (pintype "passive"))
      (node (ref "VREG") (pin "1") (pinfunction "IN_1") (pintype "power_in"))
    )
    (net (code "42") (name "Net-(XBEE-ASSOC{slash}AD5{slash}DIO5)") (class "Default")
      (node (ref "R26") (pin "2") (pinfunction "2_2") (pintype "passive"))
      (node (ref "XBEE") (pin "15") (pinfunction "ASSOC/AD5/DIO5_15") (pintype "bidirectional"))
    )
    (net (code "43") (name "Net-(XBEE-ON{slash}~{SLEEP})") (class "Default")
      (node (ref "R28") (pin "2") (pinfunction "2_2") (pintype "passive"))
      (node (ref "XBEE") (pin "13") (pinfunction "ON/~{SLEEP}_13") (pintype "output"))
    )
    (net (code "44") (name "Net-(XBEE-PWM0{slash}RSSI)") (class "Default")
      (node (ref "R27") (pin "2") (pinfunction "2_2") (pintype "passive"))
      (node (ref "XBEE") (pin "6") (pinfunction "PWM0/RSSI_6") (pintype "output"))
    )
    (net (code "45") (name "RST") (class "Default")
      (node (ref "ICSP") (pin "5") (pinfunction "5_5") (pintype "passive"))
      (node (ref "MCU") (pin "13") (pinfunction "~{RESET}_13") (pintype "bidirectional"))
      (node (ref "R23") (pin "2") (pinfunction "2_2") (pintype "passive"))
    )
    (net (code "46") (name "SCK") (class "Default")
      (node (ref "ICSP") (pin "3") (pinfunction "3_3") (pintype "passive"))
      (node (ref "MCU") (pin "9") (pinfunction "PB1(SCK)_9") (pintype "bidirectional"))
    )
    (net (code "47") (name "SCL_BM") (class "Default")
      (node (ref "BM") (pin "6") (pinfunction "SCL_6") (pintype "input"))
      (node (ref "MUX") (pin "20") (pinfunction "SC7_20") (pintype "bidirectional"))
      (node (ref "R22") (pin "1") (pinfunction "1_1") (pintype "passive"))
    )
    (net (code "48") (name "SDA_BM") (class "Default")
      (node (ref "BM") (pin "5") (pinfunction "SDA_5") (pintype "bidirectional"))
      (node (ref "MUX") (pin "19") (pinfunction "SD7_19") (pintype "bidirectional"))
      (node (ref "R21") (pin "1") (pinfunction "1_1") (pintype "passive"))
    )
    (net (code "49") (name "USB_5V0_UF") (class "Default")
      (node (ref "EXT_POWER") (pin "1") (pinfunction "1_1") (pintype "passive"))
      (node (ref "F1") (pin "1") (pinfunction "1_1") (pintype "bidirectional"))
      (node (ref "JP1") (pin "1") (pinfunction "VCC_1") (pintype "bidirectional"))
    )
    (net (code "50") (name "USB_N") (class "Default")
      (node (ref "MCU") (pin "3") (pinfunction "D-_3") (pintype "bidirectional"))
      (node (ref "R19") (pin "2") (pinfunction "2_2") (pintype "passive"))
    )
    (net (code "51") (name "USB_P") (class "Default")
      (node (ref "MCU") (pin "4") (pinfunction "D+_4") (pintype "bidirectional"))
      (node (ref "R20") (pin "2") (pinfunction "2_2") (pintype "passive"))
    )
    (net (code "52") (name "VCC_3V3") (class "Default")
      (node (ref "BARO") (pin "2") (pinfunction "VS_2") (pintype "power_in"))
      (node (ref "C1") (pin "1") (pinfunction "1_1") (pintype "passive"))
      (node (ref "C15") (pin "2") (pinfunction "2_2") (pintype "passive"))
      (node (ref "C17") (pin "+") (pinfunction "+_+") (pintype "passive"))
      (node (ref "C18") (pin "+") (pinfunction "+_+") (pintype "passive"))
      (node (ref "C19") (pin "+") (pinfunction "+_+") (pintype "passive"))
      (node (ref "C2") (pin "1") (pinfunction "1_1") (pintype "passive"))
      (node (ref "C3") (pin "1") (pinfunction "1_1") (pintype "passive"))
      (node (ref "C4") (pin "1") (pinfunction "1_1") (pintype "passive"))
      (node (ref "C5") (pin "1") (pinfunction "1_1") (pintype "passive"))
      (node (ref "C6") (pin "1") (pinfunction "1_1") (pintype "passive"))
      (node (ref "C7") (pin "+") (pinfunction "+_+") (pintype "passive"))
      (node (ref "C8") (pin "1") (pinfunction "1_1") (pintype "passive"))
      (node (ref "C9") (pin "1") (pinfunction "1_1") (pintype "passive"))
      (node (ref "DP0") (pin "2") (pinfunction "VS_2") (pintype "power_in"))
      (node (ref "DPA") (pin "2") (pinfunction "VS_2") (pintype "power_in"))
      (node (ref "DPB") (pin "2") (pinfunction "VS_2") (pintype "power_in"))
      (node (ref "EXT_OAT") (pin "1") (pinfunction "1_1") (pintype "passive"))
      (node (ref "ICSP") (pin "2") (pinfunction "2_2") (pintype "passive"))
      (node (ref "MCU") (pin "14") (pinfunction "VCC_14") (pintype "bidirectional"))
      (node (ref "MCU") (pin "24") (pinfunction "AVCC_24") (pintype "bidirectional"))
      (node (ref "MCU") (pin "34") (pinfunction "VCC_34") (pintype "bidirectional"))
      (node (ref "MCU") (pin "44") (pinfunction "AVCC_44") (pintype "bidirectional"))
      (node (ref "MUX") (pin "24") (pinfunction "VCC_24") (pintype "bidirectional"))
      (node (ref "OAT") (pin "8") (pinfunction "VCC_8") (pintype "power_in"))
      (node (ref "R1") (pin "2") (pinfunction "2_2") (pintype "passive"))
      (node (ref "R10") (pin "2") (pinfunction "2_2") (pintype "passive"))
      (node (ref "R14") (pin "2") (pinfunction "2_2") (pintype "passive"))
      (node (ref "R16") (pin "2") (pinfunction "2_2") (pintype "passive"))
      (node (ref "R17") (pin "2") (pinfunction "2_2") (pintype "passive"))
      (node (ref "R2") (pin "2") (pinfunction "2_2") (pintype "passive"))
      (node (ref "R21") (pin "2") (pinfunction "2_2") (pintype "passive"))
      (node (ref "R22") (pin "2") (pinfunction "2_2") (pintype "passive"))
      (node (ref "R23") (pin "1") (pinfunction "1_1") (pintype "passive"))
      (node (ref "R3") (pin "2") (pinfunction "2_2") (pintype "passive"))
      (node (ref "R4") (pin "2") (pinfunction "2_2") (pintype "passive"))
      (node (ref "R5") (pin "2") (pinfunction "2_2") (pintype "passive"))
      (node (ref "R6") (pin "2") (pinfunction "2_2") (pintype "passive"))
      (node (ref "R7") (pin "2") (pinfunction "2_2") (pintype "passive"))
      (node (ref "R8") (pin "2") (pinfunction "2_2") (pintype "passive"))
      (node (ref "R9") (pin "2") (pinfunction "2_2") (pintype "passive"))
      (node (ref "VREG") (pin "3") (pinfunction "OUT_3") (pintype "power_in"))
      (node (ref "XBEE") (pin "1") (pinfunction "VCC_1") (pintype "power_in"))
    )
    (net (code "53") (name "VCC_5V0") (class "Default")
      (node (ref "C13") (pin "2") (pinfunction "2_2") (pintype "passive"))
      (node (ref "CC") (pin "4") (pinfunction "VIN_4") (pintype "power_in"))
      (node (ref "F1") (pin "2") (pinfunction "2_2") (pintype "bidirectional"))
      (node (ref "MCU") (pin "2") (pinfunction "UVCC_2") (pintype "bidirectional"))
      (node (ref "MCU") (pin "7") (pinfunction "VBUS_7") (pintype "bidirectional"))
    )
    (net (code "54") (name "unconnected-(BM-PIO-Pad8)") (class "Default")
      (node (ref "BM") (pin "8") (pinfunction "PIO_8") (pintype "bidirectional"))
    )
    (net (code "55") (name "unconnected-(J1-PAD1-PadNC1)") (class "Default")
      (node (ref "J1") (pin "NC1") (pinfunction "PAD1_NC1") (pintype "bidirectional"))
    )
    (net (code "56") (name "unconnected-(J1-PAD2-PadNC2)") (class "Default")
      (node (ref "J1") (pin "NC2") (pinfunction "PAD2_NC2") (pintype "bidirectional"))
    )
    (net (code "57") (name "unconnected-(JP1-ID-Pad4)") (class "Default")
      (node (ref "JP1") (pin "4") (pinfunction "ID_4") (pintype "bidirectional"))
    )
    (net (code "58") (name "unconnected-(MCU-PB4(ADC11)-Pad28)") (class "Default")
      (node (ref "MCU") (pin "28") (pinfunction "PB4(ADC11)_28") (pintype "bidirectional"))
    )
    (net (code "59") (name "unconnected-(MCU-PB5(ADC12)-Pad29)") (class "Default")
      (node (ref "MCU") (pin "29") (pinfunction "PB5(ADC12)_29") (pintype "bidirectional"))
    )
    (net (code "60") (name "unconnected-(MCU-PB6(ADC13)-Pad30)") (class "Default")
      (node (ref "MCU") (pin "30") (pinfunction "PB6(ADC13)_30") (pintype "bidirectional"))
    )
    (net (code "61") (name "unconnected-(MCU-PB7-Pad12)") (class "Default")
      (node (ref "MCU") (pin "12") (pinfunction "PB7_12") (pintype "bidirectional"))
    )
    (net (code "62") (name "unconnected-(MCU-PC6-Pad31)") (class "Default")
      (node (ref "MCU") (pin "31") (pinfunction "PC6_31") (pintype "bidirectional"))
    )
    (net (code "63") (name "unconnected-(MCU-PC7-Pad32)") (class "Default")
      (node (ref "MCU") (pin "32") (pinfunction "PC7_32") (pintype "bidirectional"))
    )
    (net (code "64") (name "unconnected-(MCU-PD6(ADC9)-Pad26)") (class "Default")
      (node (ref "MCU") (pin "26") (pinfunction "PD6(ADC9)_26") (pintype "bidirectional"))
    )
    (net (code "65") (name "unconnected-(MCU-PD7(ADC10)-Pad27)") (class "Default")
      (node (ref "MCU") (pin "27") (pinfunction "PD7(ADC10)_27") (pintype "bidirectional"))
    )
    (net (code "66") (name "unconnected-(MCU-PE6-Pad1)") (class "Default")
      (node (ref "MCU") (pin "1") (pinfunction "PE6_1") (pintype "bidirectional"))
    )
    (net (code "67") (name "unconnected-(MCU-PF1(ADC1)-Pad40)") (class "Default")
      (node (ref "MCU") (pin "40") (pinfunction "PF1(ADC1)_40") (pintype "bidirectional"))
    )
    (net (code "68") (name "unconnected-(MCU-PF4(ADC4)-Pad39)") (class "Default")
      (node (ref "MCU") (pin "39") (pinfunction "PF4(ADC4)_39") (pintype "bidirectional"))
    )
    (net (code "69") (name "unconnected-(MCU-PF5(ADC5)-Pad38)") (class "Default")
      (node (ref "MCU") (pin "38") (pinfunction "PF5(ADC5)_38") (pintype "bidirectional"))
    )
    (net (code "70") (name "unconnected-(MCU-PF6(ADC6)-Pad37)") (class "Default")
      (node (ref "MCU") (pin "37") (pinfunction "PF6(ADC6)_37") (pintype "bidirectional"))
    )
    (net (code "71") (name "unconnected-(MCU-PF7(ADC7)-Pad36)") (class "Default")
      (node (ref "MCU") (pin "36") (pinfunction "PF7(ADC7)_36") (pintype "bidirectional"))
    )
    (net (code "72") (name "unconnected-(MUX-SC5-Pad16)") (class "Default")
      (node (ref "MUX") (pin "16") (pinfunction "SC5_16") (pintype "bidirectional"))
    )
    (net (code "73") (name "unconnected-(MUX-SC6-Pad18)") (class "Default")
      (node (ref "MUX") (pin "18") (pinfunction "SC6_18") (pintype "bidirectional"))
    )
    (net (code "74") (name "unconnected-(MUX-SD5-Pad15)") (class "Default")
      (node (ref "MUX") (pin "15") (pinfunction "SD5_15") (pintype "bidirectional"))
    )
    (net (code "75") (name "unconnected-(MUX-SD6-Pad17)") (class "Default")
      (node (ref "MUX") (pin "17") (pinfunction "SD6_17") (pintype "bidirectional"))
    )
    (net (code "76") (name "unconnected-(OAT-ALERT-Pad3)") (class "Default")
      (node (ref "OAT") (pin "3") (pinfunction "ALERT_3") (pintype "output"))
    )
    (net (code "77") (name "unconnected-(S1-S-Pad3)") (class "Default")
      (node (ref "S1") (pin "3") (pinfunction "S_3") (pintype "passive"))
    )
    (net (code "78") (name "unconnected-(XBEE-AD0{slash}DIO0-Pad20)") (class "Default")
      (node (ref "XBEE") (pin "20") (pinfunction "AD0/DIO0_20") (pintype "bidirectional"))
    )
    (net (code "79") (name "unconnected-(XBEE-AD1{slash}DIO1-Pad19)") (class "Default")
      (node (ref "XBEE") (pin "19") (pinfunction "AD1/DIO1_19") (pintype "bidirectional"))
    )
    (net (code "80") (name "unconnected-(XBEE-AD2{slash}DIO2-Pad18)") (class "Default")
      (node (ref "XBEE") (pin "18") (pinfunction "AD2/DIO2_18") (pintype "bidirectional"))
    )
    (net (code "81") (name "unconnected-(XBEE-CD{slash}DOUT_EN{slash}DO8-Pad4)") (class "Default")
      (node (ref "XBEE") (pin "4") (pinfunction "CD/DOUT_EN/DO8_4") (pintype "output"))
    )
    (net (code "82") (name "unconnected-(XBEE-COORD_SEL{slash}AD3{slash}DIO3-Pad17)") (class "Default")
      (node (ref "XBEE") (pin "17") (pinfunction "COORD_SEL/AD3/DIO3_17") (pintype "bidirectional"))
    )
    (net (code "83") (name "unconnected-(XBEE-RF_TX{slash}AD4{slash}DIO4-Pad11)") (class "Default")
      (node (ref "XBEE") (pin "11") (pinfunction "RF_TX/AD4/DIO4_11") (pintype "bidirectional"))
    )
    (net (code "84") (name "unconnected-(XBEE-VREF-Pad14)") (class "Default")
      (node (ref "XBEE") (pin "14") (pinfunction "VREF_14") (pintype "input"))
    )
    (net (code "85") (name "unconnected-(XBEE-~{CTS}{slash}DIO7-Pad12)") (class "Default")
      (node (ref "XBEE") (pin "12") (pinfunction "~{CTS}/DIO7_12") (pintype "bidirectional"))
    )
    (net (code "86") (name "unconnected-(XBEE-~{DTR}{slash}SLEEP_RQ{slash}DI8-Pad9)") (class "Default")
      (node (ref "XBEE") (pin "9") (pinfunction "~{DTR}/SLEEP_RQ/DI8_9") (pintype "bidirectional"))
    )
    (net (code "87") (name "unconnected-(XBEE-~{RESET}-Pad5)") (class "Default")
      (node (ref "XBEE") (pin "5") (pinfunction "~{RESET}_5") (pintype "input"))
    )
    (net (code "88") (name "unconnected-(XBEE-~{RTS}{slash}AD6{slash}DIO6-Pad16)") (class "Default")
      (node (ref "XBEE") (pin "16") (pinfunction "~{RTS}/AD6/DIO6_16") (pintype "bidirectional"))
    )
  )
)
